# SNES_TST_Adapter_Sheet1.net
KiCad netlist of a schematic drawn in Altium Designer
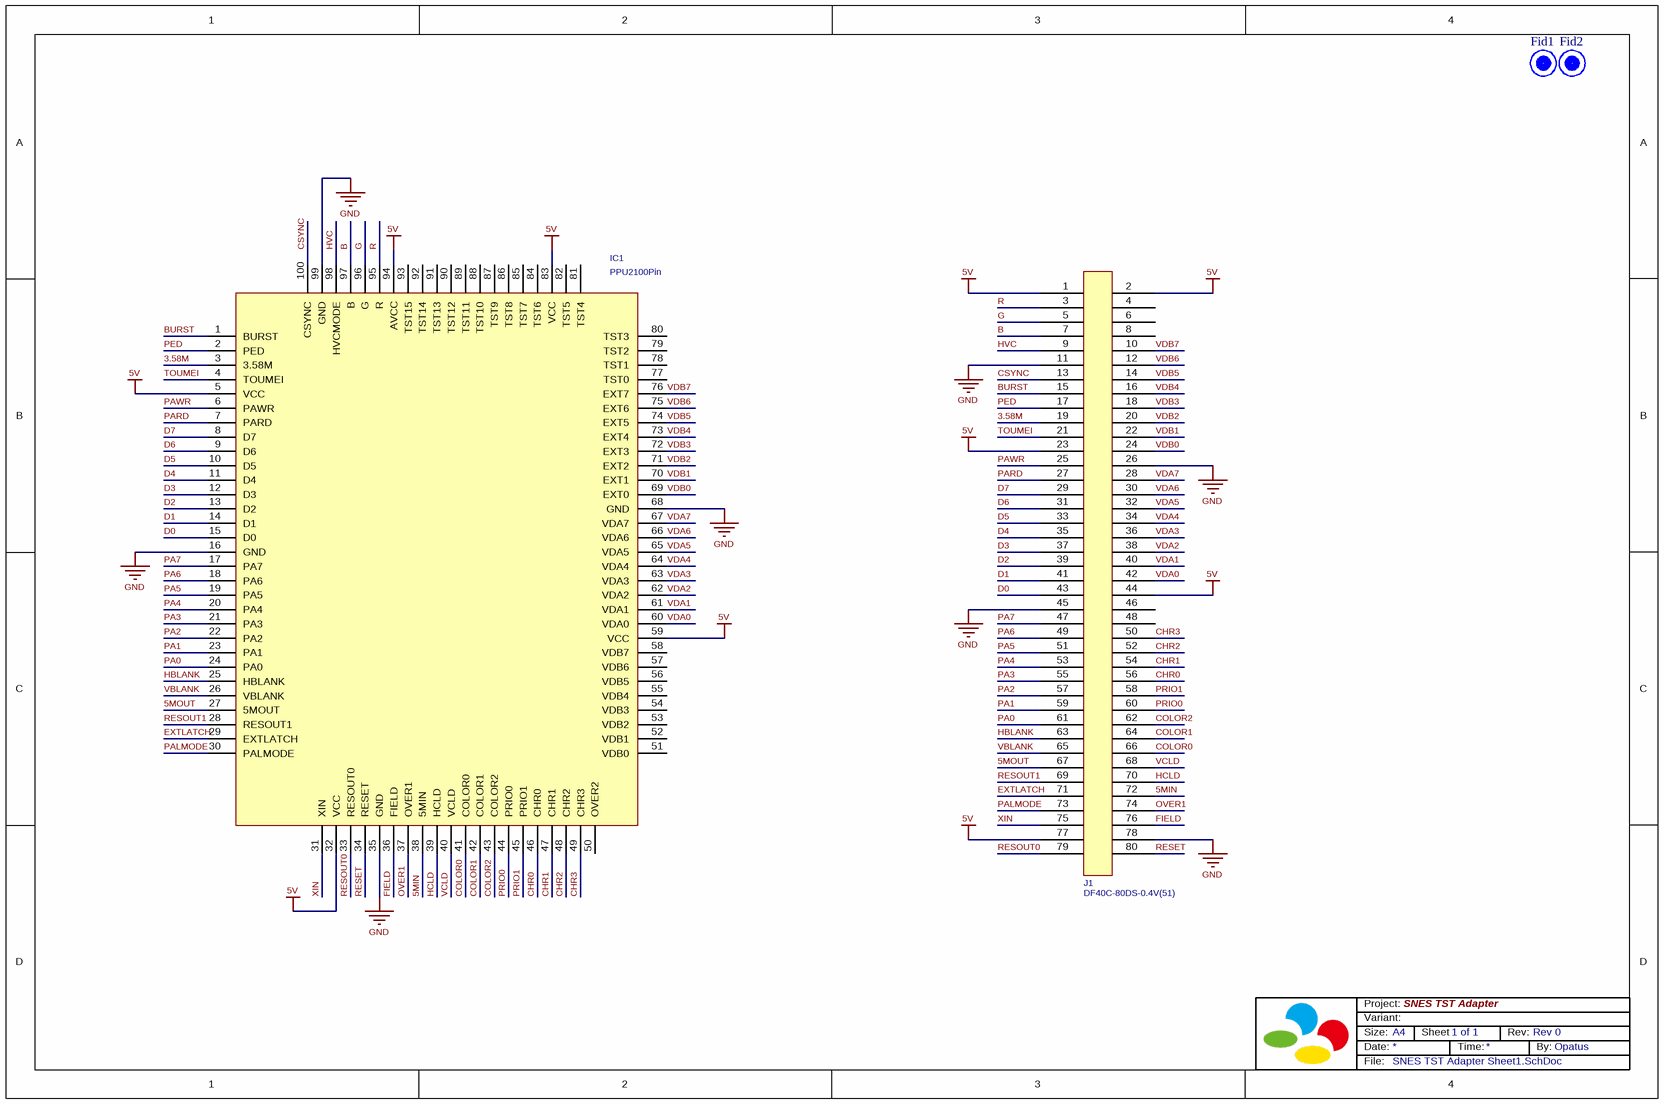
[diagram p0: SNES TST Adapter Sheet1.SchDoc]

(export (version "E")
  (design (tool "Eeschema 10.0.6"))
  (components
    (comp (ref "Fid1")
      (value "Fiducial")
      (footprint "Fiducial_1_side")
      (libsource (lib "PCB") (part "Fiducial"))
    )
    (comp (ref "Fid2")
      (value "Fiducial")
      (footprint "Fiducial_1_side")
      (libsource (lib "PCB") (part "Fiducial"))
    )
    (comp (ref "IC1")
      (value "PPU2100Pin")
      (footprint "PPU100Pin_Double")
      (description "PPU2")
      (libsource (lib "PCB") (part "PPU2100Pin"))
    )
    (comp (ref "J1")
      (value "DF40C-80DS-0.4V(51)")
      (footprint "DF40C-80DS")
      (description "80Pole Connector")
      (fields
        (field (name "MANUFACTURER") "Hirose Connector")
        (field (name "MANUFACTURER_PART_NUMBER") "DF40C-80DS-0.4V(51)")
      )
      (libsource (lib "PCB") (part "Conn 80P"))
    )
  )
  (nets
    (net (code "1") (name "/3.58M") (class "Default")
      (node (ref "IC1") (pin "3") (pinfunction "3.58M_3") (pintype "passive"))
      (node (ref "J1") (pin "19") (pintype "passive"))
    )
    (net (code "2") (name "/5MIN") (class "Default")
      (node (ref "IC1") (pin "38") (pinfunction "5MIN_38") (pintype "passive"))
      (node (ref "J1") (pin "72") (pintype "passive"))
    )
    (net (code "3") (name "/5MOUT") (class "Default")
      (node (ref "IC1") (pin "27") (pinfunction "5MOUT_27") (pintype "passive"))
      (node (ref "J1") (pin "67") (pintype "passive"))
    )
    (net (code "4") (name "/B") (class "Default")
      (node (ref "IC1") (pin "97") (pinfunction "B_97") (pintype "passive"))
      (node (ref "J1") (pin "7") (pintype "passive"))
    )
    (net (code "5") (name "/BURST") (class "Default")
      (node (ref "IC1") (pin "1") (pinfunction "BURST_1") (pintype "passive"))
      (node (ref "J1") (pin "15") (pintype "passive"))
    )
    (net (code "6") (name "/CHR0") (class "Default")
      (node (ref "IC1") (pin "46") (pinfunction "CHR0_46") (pintype "passive"))
      (node (ref "J1") (pin "56") (pintype "passive"))
    )
    (net (code "7") (name "/CHR1") (class "Default")
      (node (ref "IC1") (pin "47") (pinfunction "CHR1_47") (pintype "passive"))
      (node (ref "J1") (pin "54") (pintype "passive"))
    )
    (net (code "8") (name "/CHR2") (class "Default")
      (node (ref "IC1") (pin "48") (pinfunction "CHR2_48") (pintype "passive"))
      (node (ref "J1") (pin "52") (pintype "passive"))
    )
    (net (code "9") (name "/CHR3") (class "Default")
      (node (ref "IC1") (pin "49") (pinfunction "CHR3_49") (pintype "passive"))
      (node (ref "J1") (pin "50") (pintype "passive"))
    )
    (net (code "10") (name "/COLOR0") (class "Default")
      (node (ref "IC1") (pin "41") (pinfunction "COLOR0_41") (pintype "passive"))
      (node (ref "J1") (pin "66") (pintype "passive"))
    )
    (net (code "11") (name "/COLOR1") (class "Default")
      (node (ref "IC1") (pin "42") (pinfunction "COLOR1_42") (pintype "passive"))
      (node (ref "J1") (pin "64") (pintype "passive"))
    )
    (net (code "12") (name "/COLOR2") (class "Default")
      (node (ref "IC1") (pin "43") (pinfunction "COLOR2_43") (pintype "passive"))
      (node (ref "J1") (pin "62") (pintype "passive"))
    )
    (net (code "13") (name "/CSYNC") (class "Default")
      (node (ref "IC1") (pin "100") (pinfunction "CSYNC_100") (pintype "passive"))
      (node (ref "J1") (pin "13") (pintype "passive"))
    )
    (net (code "14") (name "/D0") (class "Default")
      (node (ref "IC1") (pin "15") (pinfunction "D0_15") (pintype "passive"))
      (node (ref "J1") (pin "43") (pintype "passive"))
    )
    (net (code "15") (name "/D1") (class "Default")
      (node (ref "IC1") (pin "14") (pinfunction "D1_14") (pintype "passive"))
      (node (ref "J1") (pin "41") (pintype "passive"))
    )
    (net (code "16") (name "/D2") (class "Default")
      (node (ref "IC1") (pin "13") (pinfunction "D2_13") (pintype "passive"))
      (node (ref "J1") (pin "39") (pintype "passive"))
    )
    (net (code "17") (name "/D3") (class "Default")
      (node (ref "IC1") (pin "12") (pinfunction "D3_12") (pintype "passive"))
      (node (ref "J1") (pin "37") (pintype "passive"))
    )
    (net (code "18") (name "/D4") (class "Default")
      (node (ref "IC1") (pin "11") (pinfunction "D4_11") (pintype "passive"))
      (node (ref "J1") (pin "35") (pintype "passive"))
    )
    (net (code "19") (name "/D5") (class "Default")
      (node (ref "IC1") (pin "10") (pinfunction "D5_10") (pintype "passive"))
      (node (ref "J1") (pin "33") (pintype "passive"))
    )
    (net (code "20") (name "/D6") (class "Default")
      (node (ref "IC1") (pin "9") (pinfunction "D6_9") (pintype "passive"))
      (node (ref "J1") (pin "31") (pintype "passive"))
    )
    (net (code "21") (name "/D7") (class "Default")
      (node (ref "IC1") (pin "8") (pinfunction "D7_8") (pintype "passive"))
      (node (ref "J1") (pin "29") (pintype "passive"))
    )
    (net (code "22") (name "/EXTLATCH") (class "Default")
      (node (ref "IC1") (pin "29") (pinfunction "EXTLATCH_29") (pintype "passive"))
      (node (ref "J1") (pin "71") (pintype "passive"))
    )
    (net (code "23") (name "/FIELD") (class "Default")
      (node (ref "IC1") (pin "36") (pinfunction "FIELD_36") (pintype "passive"))
      (node (ref "J1") (pin "76") (pintype "passive"))
    )
    (net (code "24") (name "/G") (class "Default")
      (node (ref "IC1") (pin "96") (pinfunction "G_96") (pintype "passive"))
      (node (ref "J1") (pin "5") (pintype "passive"))
    )
    (net (code "25") (name "/HBLANK") (class "Default")
      (node (ref "IC1") (pin "25") (pinfunction "HBLANK_25") (pintype "passive"))
      (node (ref "J1") (pin "63") (pintype "passive"))
    )
    (net (code "26") (name "/HCLD") (class "Default")
      (node (ref "IC1") (pin "39") (pinfunction "HCLD_39") (pintype "passive"))
      (node (ref "J1") (pin "70") (pintype "passive"))
    )
    (net (code "27") (name "/HVC") (class "Default")
      (node (ref "IC1") (pin "98") (pinfunction "HVCMODE_98") (pintype "passive"))
      (node (ref "J1") (pin "9") (pintype "passive"))
    )
    (net (code "28") (name "/OVER1") (class "Default")
      (node (ref "IC1") (pin "37") (pinfunction "OVER1_37") (pintype "passive"))
      (node (ref "J1") (pin "74") (pintype "passive"))
    )
    (net (code "29") (name "/PA0") (class "Default")
      (node (ref "IC1") (pin "24") (pinfunction "PA0_24") (pintype "passive"))
      (node (ref "J1") (pin "61") (pintype "passive"))
    )
    (net (code "30") (name "/PA1") (class "Default")
      (node (ref "IC1") (pin "23") (pinfunction "PA1_23") (pintype "passive"))
      (node (ref "J1") (pin "59") (pintype "passive"))
    )
    (net (code "31") (name "/PA2") (class "Default")
      (node (ref "IC1") (pin "22") (pinfunction "PA2_22") (pintype "passive"))
      (node (ref "J1") (pin "57") (pintype "passive"))
    )
    (net (code "32") (name "/PA3") (class "Default")
      (node (ref "IC1") (pin "21") (pinfunction "PA3_21") (pintype "passive"))
      (node (ref "J1") (pin "55") (pintype "passive"))
    )
    (net (code "33") (name "/PA4") (class "Default")
      (node (ref "IC1") (pin "20") (pinfunction "PA4_20") (pintype "passive"))
      (node (ref "J1") (pin "53") (pintype "passive"))
    )
    (net (code "34") (name "/PA5") (class "Default")
      (node (ref "IC1") (pin "19") (pinfunction "PA5_19") (pintype "passive"))
      (node (ref "J1") (pin "51") (pintype "passive"))
    )
    (net (code "35") (name "/PA6") (class "Default")
      (node (ref "IC1") (pin "18") (pinfunction "PA6_18") (pintype "passive"))
      (node (ref "J1") (pin "49") (pintype "passive"))
    )
    (net (code "36") (name "/PA7") (class "Default")
      (node (ref "IC1") (pin "17") (pinfunction "PA7_17") (pintype "passive"))
      (node (ref "J1") (pin "47") (pintype "passive"))
    )
    (net (code "37") (name "/PALMODE") (class "Default")
      (node (ref "IC1") (pin "30") (pinfunction "PALMODE_30") (pintype "passive"))
      (node (ref "J1") (pin "73") (pintype "passive"))
    )
    (net (code "38") (name "/PARD") (class "Default")
      (node (ref "IC1") (pin "7") (pinfunction "PARD_7") (pintype "passive"))
      (node (ref "J1") (pin "27") (pintype "passive"))
    )
    (net (code "39") (name "/PAWR") (class "Default")
      (node (ref "IC1") (pin "6") (pinfunction "PAWR_6") (pintype "passive"))
      (node (ref "J1") (pin "25") (pintype "passive"))
    )
    (net (code "40") (name "/PED") (class "Default")
      (node (ref "IC1") (pin "2") (pinfunction "PED_2") (pintype "passive"))
      (node (ref "J1") (pin "17") (pintype "passive"))
    )
    (net (code "41") (name "/PRIO0") (class "Default")
      (node (ref "IC1") (pin "44") (pinfunction "PRIO0_44") (pintype "passive"))
      (node (ref "J1") (pin "60") (pintype "passive"))
    )
    (net (code "42") (name "/PRIO1") (class "Default")
      (node (ref "IC1") (pin "45") (pinfunction "PRIO1_45") (pintype "passive"))
      (node (ref "J1") (pin "58") (pintype "passive"))
    )
    (net (code "43") (name "/R") (class "Default")
      (node (ref "IC1") (pin "95") (pinfunction "R_95") (pintype "passive"))
      (node (ref "J1") (pin "3") (pintype "passive"))
    )
    (net (code "44") (name "/RESET") (class "Default")
      (node (ref "IC1") (pin "34") (pinfunction "RESET_34") (pintype "passive"))
      (node (ref "J1") (pin "80") (pintype "passive"))
    )
    (net (code "45") (name "/RESOUT0") (class "Default")
      (node (ref "IC1") (pin "33") (pinfunction "RESOUT0_33") (pintype "passive"))
      (node (ref "J1") (pin "79") (pintype "passive"))
    )
    (net (code "46") (name "/RESOUT1") (class "Default")
      (node (ref "IC1") (pin "28") (pinfunction "RESOUT1_28") (pintype "passive"))
      (node (ref "J1") (pin "69") (pintype "passive"))
    )
    (net (code "47") (name "/TOUMEI") (class "Default")
      (node (ref "IC1") (pin "4") (pinfunction "TOUMEI_4") (pintype "passive"))
      (node (ref "J1") (pin "21") (pintype "passive"))
    )
    (net (code "48") (name "/VBLANK") (class "Default")
      (node (ref "IC1") (pin "26") (pinfunction "VBLANK_26") (pintype "passive"))
      (node (ref "J1") (pin "65") (pintype "passive"))
    )
    (net (code "49") (name "/VCLD") (class "Default")
      (node (ref "IC1") (pin "40") (pinfunction "VCLD_40") (pintype "passive"))
      (node (ref "J1") (pin "68") (pintype "passive"))
    )
    (net (code "50") (name "/VDA0") (class "Default")
      (node (ref "IC1") (pin "60") (pinfunction "VDA0_60") (pintype "passive"))
      (node (ref "J1") (pin "42") (pintype "passive"))
    )
    (net (code "51") (name "/VDA1") (class "Default")
      (node (ref "IC1") (pin "61") (pinfunction "VDA1_61") (pintype "passive"))
      (node (ref "J1") (pin "40") (pintype "passive"))
    )
    (net (code "52") (name "/VDA2") (class "Default")
      (node (ref "IC1") (pin "62") (pinfunction "VDA2_62") (pintype "passive"))
      (node (ref "J1") (pin "38") (pintype "passive"))
    )
    (net (code "53") (name "/VDA3") (class "Default")
      (node (ref "IC1") (pin "63") (pinfunction "VDA3_63") (pintype "passive"))
      (node (ref "J1") (pin "36") (pintype "passive"))
    )
    (net (code "54") (name "/VDA4") (class "Default")
      (node (ref "IC1") (pin "64") (pinfunction "VDA4_64") (pintype "passive"))
      (node (ref "J1") (pin "34") (pintype "passive"))
    )
    (net (code "55") (name "/VDA5") (class "Default")
      (node (ref "IC1") (pin "65") (pinfunction "VDA5_65") (pintype "passive"))
      (node (ref "J1") (pin "32") (pintype "passive"))
    )
    (net (code "56") (name "/VDA6") (class "Default")
      (node (ref "IC1") (pin "66") (pinfunction "VDA6_66") (pintype "passive"))
      (node (ref "J1") (pin "30") (pintype "passive"))
    )
    (net (code "57") (name "/VDA7") (class "Default")
      (node (ref "IC1") (pin "67") (pinfunction "VDA7_67") (pintype "passive"))
      (node (ref "J1") (pin "28") (pintype "passive"))
    )
    (net (code "58") (name "/VDB0") (class "Default")
      (node (ref "IC1") (pin "69") (pinfunction "EXT0_69") (pintype "passive"))
      (node (ref "J1") (pin "24") (pintype "passive"))
    )
    (net (code "59") (name "/VDB1") (class "Default")
      (node (ref "IC1") (pin "70") (pinfunction "EXT1_70") (pintype "passive"))
      (node (ref "J1") (pin "22") (pintype "passive"))
    )
    (net (code "60") (name "/VDB2") (class "Default")
      (node (ref "IC1") (pin "71") (pinfunction "EXT2_71") (pintype "passive"))
      (node (ref "J1") (pin "20") (pintype "passive"))
    )
    (net (code "61") (name "/VDB3") (class "Default")
      (node (ref "IC1") (pin "72") (pinfunction "EXT3_72") (pintype "passive"))
      (node (ref "J1") (pin "18") (pintype "passive"))
    )
    (net (code "62") (name "/VDB4") (class "Default")
      (node (ref "IC1") (pin "73") (pinfunction "EXT4_73") (pintype "passive"))
      (node (ref "J1") (pin "16") (pintype "passive"))
    )
    (net (code "63") (name "/VDB5") (class "Default")
      (node (ref "IC1") (pin "74") (pinfunction "EXT5_74") (pintype "passive"))
      (node (ref "J1") (pin "14") (pintype "passive"))
    )
    (net (code "64") (name "/VDB6") (class "Default")
      (node (ref "IC1") (pin "75") (pinfunction "EXT6_75") (pintype "passive"))
      (node (ref "J1") (pin "12") (pintype "passive"))
    )
    (net (code "65") (name "/VDB7") (class "Default")
      (node (ref "IC1") (pin "76") (pinfunction "EXT7_76") (pintype "passive"))
      (node (ref "J1") (pin "10") (pintype "passive"))
    )
    (net (code "66") (name "/XIN") (class "Default")
      (node (ref "IC1") (pin "31") (pinfunction "XIN_31") (pintype "passive"))
      (node (ref "J1") (pin "75") (pintype "passive"))
    )
    (net (code "67") (name "5V") (class "Default")
      (node (ref "IC1") (pin "32") (pinfunction "VCC_32") (pintype "passive"))
      (node (ref "IC1") (pin "5") (pinfunction "VCC_5") (pintype "passive"))
      (node (ref "IC1") (pin "59") (pinfunction "VCC_59") (pintype "passive"))
      (node (ref "IC1") (pin "83") (pinfunction "VCC_83") (pintype "passive"))
      (node (ref "IC1") (pin "94") (pinfunction "AVCC_94") (pintype "passive"))
      (node (ref "J1") (pin "1") (pintype "passive"))
      (node (ref "J1") (pin "2") (pintype "passive"))
      (node (ref "J1") (pin "23") (pintype "passive"))
      (node (ref "J1") (pin "44") (pintype "passive"))
      (node (ref "J1") (pin "77") (pintype "passive"))
    )
    (net (code "68") (name "GND") (class "Default")
      (node (ref "IC1") (pin "16") (pinfunction "GND_16") (pintype "passive"))
      (node (ref "IC1") (pin "35") (pinfunction "GND_35") (pintype "passive"))
      (node (ref "IC1") (pin "68") (pinfunction "GND_68") (pintype "passive"))
      (node (ref "IC1") (pin "99") (pinfunction "GND_99") (pintype "passive"))
      (node (ref "J1") (pin "11") (pintype "passive"))
      (node (ref "J1") (pin "26") (pintype "passive"))
      (node (ref "J1") (pin "45") (pintype "passive"))
      (node (ref "J1") (pin "78") (pintype "passive"))
    )
    (net (code "69") (name "unconnected-(IC1-OVER2-Pad50)") (class "Default")
      (node (ref "IC1") (pin "50") (pinfunction "OVER2_50") (pintype "passive"))
    )
    (net (code "70") (name "unconnected-(IC1-TST0-Pad77)") (class "Default")
      (node (ref "IC1") (pin "77") (pinfunction "TST0_77") (pintype "passive"))
    )
    (net (code "71") (name "unconnected-(IC1-TST1-Pad78)") (class "Default")
      (node (ref "IC1") (pin "78") (pinfunction "TST1_78") (pintype "passive"))
    )
    (net (code "72") (name "unconnected-(IC1-TST2-Pad79)") (class "Default")
      (node (ref "IC1") (pin "79") (pinfunction "TST2_79") (pintype "passive"))
    )
    (net (code "73") (name "unconnected-(IC1-TST3-Pad80)") (class "Default")
      (node (ref "IC1") (pin "80") (pinfunction "TST3_80") (pintype "passive"))
    )
    (net (code "74") (name "unconnected-(IC1-TST4-Pad81)") (class "Default")
      (node (ref "IC1") (pin "81") (pinfunction "TST4_81") (pintype "passive"))
    )
    (net (code "75") (name "unconnected-(IC1-TST5-Pad82)") (class "Default")
      (node (ref "IC1") (pin "82") (pinfunction "TST5_82") (pintype "passive"))
    )
    (net (code "76") (name "unconnected-(IC1-TST6-Pad84)") (class "Default")
      (node (ref "IC1") (pin "84") (pinfunction "TST6_84") (pintype "passive"))
    )
    (net (code "77") (name "unconnected-(IC1-TST7-Pad85)") (class "Default")
      (node (ref "IC1") (pin "85") (pinfunction "TST7_85") (pintype "passive"))
    )
    (net (code "78") (name "unconnected-(IC1-TST8-Pad86)") (class "Default")
      (node (ref "IC1") (pin "86") (pinfunction "TST8_86") (pintype "passive"))
    )
    (net (code "79") (name "unconnected-(IC1-TST9-Pad87)") (class "Default")
      (node (ref "IC1") (pin "87") (pinfunction "TST9_87") (pintype "passive"))
    )
    (net (code "80") (name "unconnected-(IC1-TST10-Pad88)") (class "Default")
      (node (ref "IC1") (pin "88") (pinfunction "TST10_88") (pintype "passive"))
    )
    (net (code "81") (name "unconnected-(IC1-TST11-Pad89)") (class "Default")
      (node (ref "IC1") (pin "89") (pinfunction "TST11_89") (pintype "passive"))
    )
    (net (code "82") (name "unconnected-(IC1-TST12-Pad90)") (class "Default")
      (node (ref "IC1") (pin "90") (pinfunction "TST12_90") (pintype "passive"))
    )
    (net (code "83") (name "unconnected-(IC1-TST13-Pad91)") (class "Default")
      (node (ref "IC1") (pin "91") (pinfunction "TST13_91") (pintype "passive"))
    )
    (net (code "84") (name "unconnected-(IC1-TST14-Pad92)") (class "Default")
      (node (ref "IC1") (pin "92") (pinfunction "TST14_92") (pintype "passive"))
    )
    (net (code "85") (name "unconnected-(IC1-TST15-Pad93)") (class "Default")
      (node (ref "IC1") (pin "93") (pinfunction "TST15_93") (pintype "passive"))
    )
    (net (code "86") (name "unconnected-(IC1-VDB0-Pad51)") (class "Default")
      (node (ref "IC1") (pin "51") (pinfunction "VDB0_51") (pintype "passive"))
    )
    (net (code "87") (name "unconnected-(IC1-VDB1-Pad52)") (class "Default")
      (node (ref "IC1") (pin "52") (pinfunction "VDB1_52") (pintype "passive"))
    )
    (net (code "88") (name "unconnected-(IC1-VDB2-Pad53)") (class "Default")
      (node (ref "IC1") (pin "53") (pinfunction "VDB2_53") (pintype "passive"))
    )
    (net (code "89") (name "unconnected-(IC1-VDB3-Pad54)") (class "Default")
      (node (ref "IC1") (pin "54") (pinfunction "VDB3_54") (pintype "passive"))
    )
    (net (code "90") (name "unconnected-(IC1-VDB4-Pad55)") (class "Default")
      (node (ref "IC1") (pin "55") (pinfunction "VDB4_55") (pintype "passive"))
    )
    (net (code "91") (name "unconnected-(IC1-VDB5-Pad56)") (class "Default")
      (node (ref "IC1") (pin "56") (pinfunction "VDB5_56") (pintype "passive"))
    )
    (net (code "92") (name "unconnected-(IC1-VDB6-Pad57)") (class "Default")
      (node (ref "IC1") (pin "57") (pinfunction "VDB6_57") (pintype "passive"))
    )
    (net (code "93") (name "unconnected-(IC1-VDB7-Pad58)") (class "Default")
      (node (ref "IC1") (pin "58") (pinfunction "VDB7_58") (pintype "passive"))
    )
    (net (code "94") (name "unconnected-(J1-Pad4)") (class "Default")
      (node (ref "J1") (pin "4") (pintype "passive"))
    )
    (net (code "95") (name "unconnected-(J1-Pad6)") (class "Default")
      (node (ref "J1") (pin "6") (pintype "passive"))
    )
    (net (code "96") (name "unconnected-(J1-Pad8)") (class "Default")
      (node (ref "J1") (pin "8") (pintype "passive"))
    )
    (net (code "97") (name "unconnected-(J1-Pad46)") (class "Default")
      (node (ref "J1") (pin "46") (pintype "passive"))
    )
    (net (code "98") (name "unconnected-(J1-Pad48)") (class "Default")
      (node (ref "J1") (pin "48") (pintype "passive"))
    )
  )
)
